# board.net
KiCad netlist of a schematic drawn in EAGLE
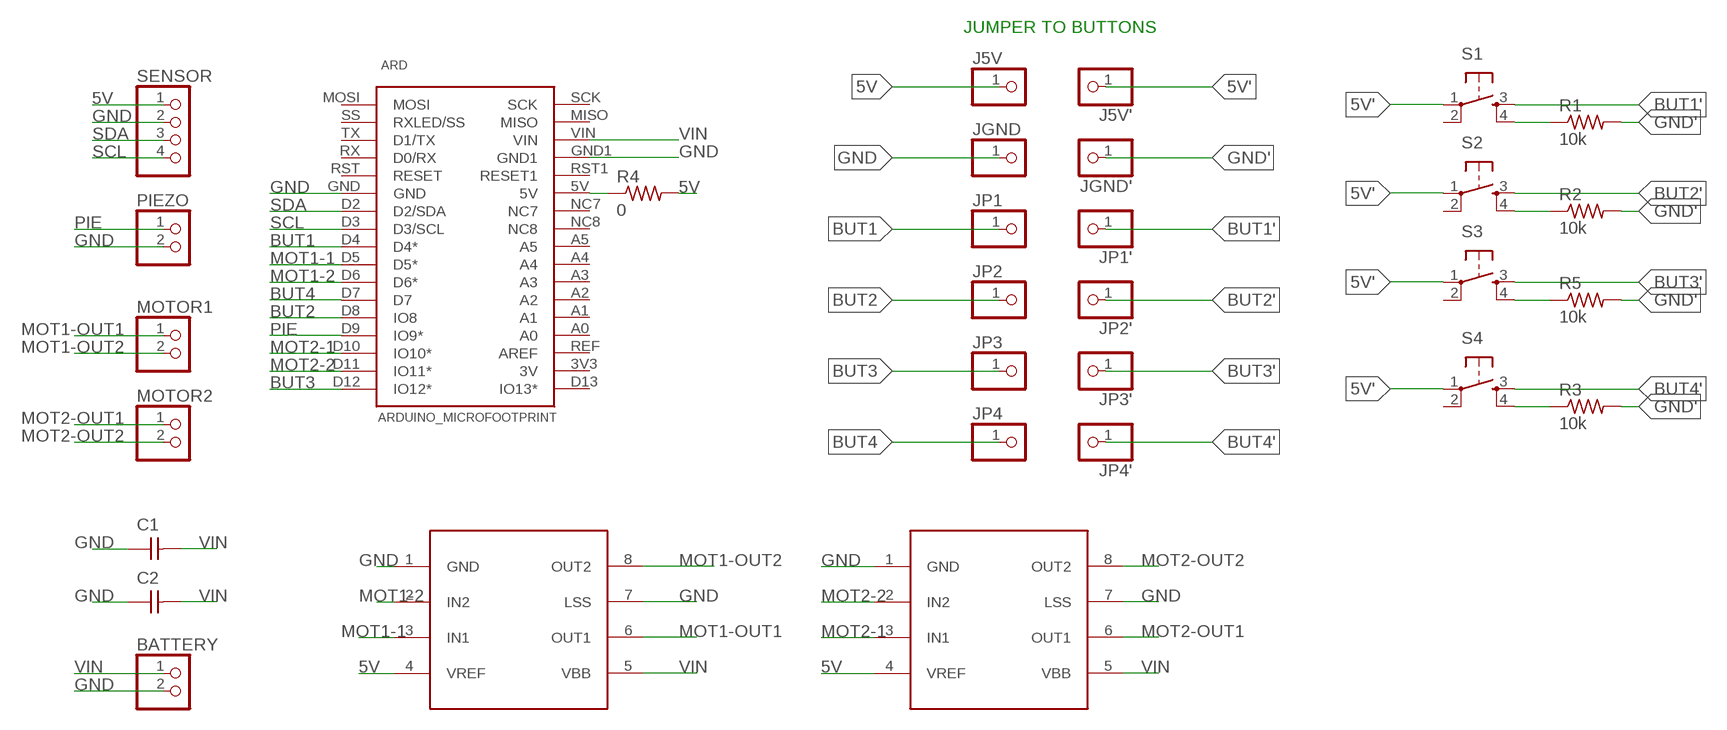
[diagram p0: schematic, sheet 1]

(export (version "E")
  (design (tool "Eeschema 10.0.6"))
  (components
    (comp (ref "ARD")
      (value "ARDUINO_MICROFOOTPRINT")
      (footprint "eagle-import:ARDUINO-MICRO")
      (libsource (lib "eagle-import") (part "ARDUINO_MICROFOOTPRINT"))
    )
    (comp (ref "BATTERY")
      (value "PINHD-1X2")
      (footprint "eagle-import:1X02")
      (libsource (lib "eagle-import") (part "PINHD-1X2"))
    )
    (comp (ref "C1")
      (value "CAP-UNPOLARIZEDFAB")
      (footprint "eagle-import:C1206FAB")
      (libsource (lib "eagle-import") (part "CAP-UNPOLARIZEDFAB"))
    )
    (comp (ref "C2")
      (value "CAP-UNPOLARIZEDFAB")
      (footprint "eagle-import:C1206FAB")
      (libsource (lib "eagle-import") (part "CAP-UNPOLARIZEDFAB"))
    )
    (comp (ref "J5V")
      (value "PINHD-1X1")
      (footprint "eagle-import:1X01")
      (libsource (lib "eagle-import") (part "PINHD-1X1"))
    )
    (comp (ref "J5V'")
      (value "PINHD-1X1")
      (footprint "eagle-import:1X01")
      (libsource (lib "eagle-import") (part "PINHD-1X1"))
    )
    (comp (ref "JGND")
      (value "PINHD-1X1")
      (footprint "eagle-import:1X01")
      (libsource (lib "eagle-import") (part "PINHD-1X1"))
    )
    (comp (ref "JGND'")
      (value "PINHD-1X1")
      (footprint "eagle-import:1X01")
      (libsource (lib "eagle-import") (part "PINHD-1X1"))
    )
    (comp (ref "JP1")
      (value "PINHD-1X1")
      (footprint "eagle-import:1X01")
      (libsource (lib "eagle-import") (part "PINHD-1X1"))
    )
    (comp (ref "JP1'")
      (value "PINHD-1X1")
      (footprint "eagle-import:1X01")
      (libsource (lib "eagle-import") (part "PINHD-1X1"))
    )
    (comp (ref "JP2")
      (value "PINHD-1X1")
      (footprint "eagle-import:1X01")
      (libsource (lib "eagle-import") (part "PINHD-1X1"))
    )
    (comp (ref "JP2'")
      (value "PINHD-1X1")
      (footprint "eagle-import:1X01")
      (libsource (lib "eagle-import") (part "PINHD-1X1"))
    )
    (comp (ref "JP3")
      (value "PINHD-1X1")
      (footprint "eagle-import:1X01")
      (libsource (lib "eagle-import") (part "PINHD-1X1"))
    )
    (comp (ref "JP3'")
      (value "PINHD-1X1")
      (footprint "eagle-import:1X01")
      (libsource (lib "eagle-import") (part "PINHD-1X1"))
    )
    (comp (ref "JP4")
      (value "PINHD-1X1")
      (footprint "eagle-import:1X01")
      (libsource (lib "eagle-import") (part "PINHD-1X1"))
    )
    (comp (ref "JP4'")
      (value "PINHD-1X1")
      (footprint "eagle-import:1X01")
      (libsource (lib "eagle-import") (part "PINHD-1X1"))
    )
    (comp (ref "MOT1")
      (value "A4953-H-BRIDGE-MOTOR-DRIVER")
      (footprint "eagle-import:SOIC8")
      (libsource (lib "eagle-import") (part "A4953-H-BRIDGE-MOTOR-DRIVER"))
    )
    (comp (ref "MOT2")
      (value "A4953-H-BRIDGE-MOTOR-DRIVER")
      (footprint "eagle-import:SOIC8")
      (libsource (lib "eagle-import") (part "A4953-H-BRIDGE-MOTOR-DRIVER"))
    )
    (comp (ref "MOTOR1")
      (value "PINHD-1X2")
      (footprint "eagle-import:1X02")
      (libsource (lib "eagle-import") (part "PINHD-1X2"))
    )
    (comp (ref "MOTOR2")
      (value "PINHD-1X2")
      (footprint "eagle-import:1X02")
      (libsource (lib "eagle-import") (part "PINHD-1X2"))
    )
    (comp (ref "PIEZO")
      (value "PINHD-1X2")
      (footprint "eagle-import:1X02")
      (libsource (lib "eagle-import") (part "PINHD-1X2"))
    )
    (comp (ref "R1")
      (value "10k")
      (footprint "eagle-import:R1206FAB")
      (libsource (lib "eagle-import") (part "RES-US1206FAB"))
    )
    (comp (ref "R2")
      (value "10k")
      (footprint "eagle-import:R1206FAB")
      (libsource (lib "eagle-import") (part "RES-US1206FAB"))
    )
    (comp (ref "R3")
      (value "10k")
      (footprint "eagle-import:R1206FAB")
      (libsource (lib "eagle-import") (part "RES-US1206FAB"))
    )
    (comp (ref "R4")
      (value "0")
      (footprint "eagle-import:R1206FAB")
      (libsource (lib "eagle-import") (part "RES-US1206FAB"))
    )
    (comp (ref "R5")
      (value "10k")
      (footprint "eagle-import:R1206FAB")
      (libsource (lib "eagle-import") (part "RES-US1206FAB"))
    )
    (comp (ref "S1")
      (value "6MM_SWITCH6MM_SWITCH")
      (footprint "eagle-import:6MM_SWITCH")
      (libsource (lib "eagle-import") (part "6MM_SWITCH6MM_SWITCH"))
    )
    (comp (ref "S2")
      (value "6MM_SWITCH6MM_SWITCH")
      (footprint "eagle-import:6MM_SWITCH")
      (libsource (lib "eagle-import") (part "6MM_SWITCH6MM_SWITCH"))
    )
    (comp (ref "S3")
      (value "6MM_SWITCH6MM_SWITCH")
      (footprint "eagle-import:6MM_SWITCH")
      (libsource (lib "eagle-import") (part "6MM_SWITCH6MM_SWITCH"))
    )
    (comp (ref "S4")
      (value "6MM_SWITCH6MM_SWITCH")
      (footprint "eagle-import:6MM_SWITCH")
      (libsource (lib "eagle-import") (part "6MM_SWITCH6MM_SWITCH"))
    )
    (comp (ref "SENSOR")
      (value "PINHD-1X4")
      (footprint "eagle-import:1X04")
      (libsource (lib "eagle-import") (part "PINHD-1X4"))
    )
  )
  (nets
    (net (code "1") (name "/MOT1-1") (class "Default")
      (node (ref "ARD") (pin "D5") (pinfunction "D5*_D5") (pintype "bidirectional"))
      (node (ref "MOT1") (pin "3") (pinfunction "IN1_3") (pintype "bidirectional"))
    )
    (net (code "2") (name "/MOT1-2") (class "Default")
      (node (ref "ARD") (pin "D6") (pinfunction "D6*_D6") (pintype "bidirectional"))
      (node (ref "MOT1") (pin "2") (pinfunction "IN2_2") (pintype "bidirectional"))
    )
    (net (code "3") (name "/MOT1-OUT1") (class "Default")
      (node (ref "MOT1") (pin "6") (pinfunction "OUT1_6") (pintype "bidirectional"))
      (node (ref "MOTOR1") (pin "1") (pinfunction "1_1") (pintype "passive"))
    )
    (net (code "4") (name "/MOT1-OUT2") (class "Default")
      (node (ref "MOT1") (pin "8") (pinfunction "OUT2_8") (pintype "bidirectional"))
      (node (ref "MOTOR1") (pin "2") (pinfunction "2_2") (pintype "passive"))
    )
    (net (code "5") (name "/MOT2-1") (class "Default")
      (node (ref "ARD") (pin "D10") (pinfunction "IO10*_D10") (pintype "bidirectional"))
      (node (ref "MOT2") (pin "3") (pinfunction "IN1_3") (pintype "bidirectional"))
    )
    (net (code "6") (name "/MOT2-2") (class "Default")
      (node (ref "ARD") (pin "D11") (pinfunction "IO11*_D11") (pintype "bidirectional"))
      (node (ref "MOT2") (pin "2") (pinfunction "IN2_2") (pintype "bidirectional"))
    )
    (net (code "7") (name "/MOT2-OUT1") (class "Default")
      (node (ref "MOT2") (pin "6") (pinfunction "OUT1_6") (pintype "bidirectional"))
      (node (ref "MOTOR2") (pin "1") (pinfunction "1_1") (pintype "passive"))
    )
    (net (code "8") (name "/MOT2-OUT2") (class "Default")
      (node (ref "MOT2") (pin "8") (pinfunction "OUT2_8") (pintype "bidirectional"))
      (node (ref "MOTOR2") (pin "2") (pinfunction "2_2") (pintype "passive"))
    )
    (net (code "9") (name "/PIE") (class "Default")
      (node (ref "ARD") (pin "D9") (pinfunction "IO9*_D9") (pintype "bidirectional"))
      (node (ref "PIEZO") (pin "1") (pinfunction "1_1") (pintype "passive"))
    )
    (net (code "10") (name "/SCL") (class "Default")
      (node (ref "ARD") (pin "D3") (pinfunction "D3/SCL_D3") (pintype "bidirectional"))
      (node (ref "SENSOR") (pin "4") (pinfunction "4_4") (pintype "passive"))
    )
    (net (code "11") (name "/SDA") (class "Default")
      (node (ref "ARD") (pin "D2") (pinfunction "D2/SDA_D2") (pintype "bidirectional"))
      (node (ref "SENSOR") (pin "3") (pinfunction "3_3") (pintype "passive"))
    )
    (net (code "12") (name "/VIN") (class "Default")
      (node (ref "ARD") (pin "VIN") (pinfunction "VIN_VIN") (pintype "bidirectional"))
      (node (ref "BATTERY") (pin "1") (pinfunction "1_1") (pintype "passive"))
      (node (ref "C1") (pin "2") (pinfunction "2_2") (pintype "passive"))
      (node (ref "C2") (pin "2") (pinfunction "2_2") (pintype "passive"))
      (node (ref "MOT1") (pin "5") (pinfunction "VBB_5") (pintype "bidirectional"))
      (node (ref "MOT2") (pin "5") (pinfunction "VBB_5") (pintype "bidirectional"))
    )
    (net (code "13") (name "5V") (class "Default")
      (node (ref "J5V") (pin "1") (pinfunction "1_1") (pintype "passive"))
      (node (ref "MOT1") (pin "4") (pinfunction "VREF_4") (pintype "bidirectional"))
      (node (ref "MOT2") (pin "4") (pinfunction "VREF_4") (pintype "bidirectional"))
      (node (ref "R4") (pin "2") (pinfunction "2_2") (pintype "passive"))
      (node (ref "SENSOR") (pin "1") (pinfunction "1_1") (pintype "passive"))
    )
    (net (code "14") (name "5V'") (class "Default")
      (node (ref "J5V'") (pin "1") (pinfunction "1_1") (pintype "passive"))
      (node (ref "S1") (pin "1") (pinfunction "P_1") (pintype "passive"))
      (node (ref "S2") (pin "1") (pinfunction "P_1") (pintype "passive"))
      (node (ref "S3") (pin "1") (pinfunction "P_1") (pintype "passive"))
      (node (ref "S4") (pin "1") (pinfunction "P_1") (pintype "passive"))
    )
    (net (code "15") (name "BUT1") (class "Default")
      (node (ref "ARD") (pin "D4") (pinfunction "D4*_D4") (pintype "bidirectional"))
      (node (ref "JP1") (pin "1") (pinfunction "1_1") (pintype "passive"))
    )
    (net (code "16") (name "BUT1'") (class "Default")
      (node (ref "JP1'") (pin "1") (pinfunction "1_1") (pintype "passive"))
      (node (ref "S1") (pin "3") (pinfunction "S_3") (pintype "passive"))
    )
    (net (code "17") (name "BUT2") (class "Default")
      (node (ref "ARD") (pin "D8") (pinfunction "IO8_D8") (pintype "bidirectional"))
      (node (ref "JP2") (pin "1") (pinfunction "1_1") (pintype "passive"))
    )
    (net (code "18") (name "BUT2'") (class "Default")
      (node (ref "JP2'") (pin "1") (pinfunction "1_1") (pintype "passive"))
      (node (ref "S2") (pin "3") (pinfunction "S_3") (pintype "passive"))
    )
    (net (code "19") (name "BUT3") (class "Default")
      (node (ref "ARD") (pin "D12") (pinfunction "IO12*_D12") (pintype "bidirectional"))
      (node (ref "JP3") (pin "1") (pinfunction "1_1") (pintype "passive"))
    )
    (net (code "20") (name "BUT3'") (class "Default")
      (node (ref "JP3'") (pin "1") (pinfunction "1_1") (pintype "passive"))
      (node (ref "S3") (pin "3") (pinfunction "S_3") (pintype "passive"))
    )
    (net (code "21") (name "BUT4") (class "Default")
      (node (ref "ARD") (pin "D7") (pinfunction "D7_D7") (pintype "bidirectional"))
      (node (ref "JP4") (pin "1") (pinfunction "1_1") (pintype "passive"))
    )
    (net (code "22") (name "BUT4'") (class "Default")
      (node (ref "JP4'") (pin "1") (pinfunction "1_1") (pintype "passive"))
      (node (ref "S4") (pin "3") (pinfunction "S_3") (pintype "passive"))
    )
    (net (code "23") (name "GND") (class "Default")
      (node (ref "ARD") (pin "GND") (pinfunction "GND_GND") (pintype "bidirectional"))
      (node (ref "ARD") (pin "GND1") (pinfunction "GND1_GND1") (pintype "bidirectional"))
      (node (ref "BATTERY") (pin "2") (pinfunction "2_2") (pintype "passive"))
      (node (ref "C1") (pin "1") (pinfunction "1_1") (pintype "passive"))
      (node (ref "C2") (pin "1") (pinfunction "1_1") (pintype "passive"))
      (node (ref "JGND") (pin "1") (pinfunction "1_1") (pintype "passive"))
      (node (ref "MOT1") (pin "1") (pinfunction "GND_1") (pintype "bidirectional"))
      (node (ref "MOT1") (pin "7") (pinfunction "LSS_7") (pintype "bidirectional"))
      (node (ref "MOT2") (pin "1") (pinfunction "GND_1") (pintype "bidirectional"))
      (node (ref "MOT2") (pin "7") (pinfunction "LSS_7") (pintype "bidirectional"))
      (node (ref "PIEZO") (pin "2") (pinfunction "2_2") (pintype "passive"))
      (node (ref "SENSOR") (pin "2") (pinfunction "2_2") (pintype "passive"))
    )
    (net (code "24") (name "GND'") (class "Default")
      (node (ref "JGND'") (pin "1") (pinfunction "1_1") (pintype "passive"))
      (node (ref "R1") (pin "2") (pinfunction "2_2") (pintype "passive"))
      (node (ref "R2") (pin "2") (pinfunction "2_2") (pintype "passive"))
      (node (ref "R3") (pin "2") (pinfunction "2_2") (pintype "passive"))
      (node (ref "R5") (pin "2") (pinfunction "2_2") (pintype "passive"))
    )
    (net (code "25") (name "Net-(ARD-Pad5V)") (class "Default")
      (node (ref "ARD") (pin "5V") (pinfunction "5V_5V") (pintype "bidirectional"))
      (node (ref "R4") (pin "1") (pinfunction "1_1") (pintype "passive"))
    )
    (net (code "26") (name "Net-(S1-S1)") (class "Default")
      (node (ref "R1") (pin "1") (pinfunction "1_1") (pintype "passive"))
      (node (ref "S1") (pin "4") (pinfunction "S1_4") (pintype "passive"))
    )
    (net (code "27") (name "Net-(S2-S1)") (class "Default")
      (node (ref "R2") (pin "1") (pinfunction "1_1") (pintype "passive"))
      (node (ref "S2") (pin "4") (pinfunction "S1_4") (pintype "passive"))
    )
    (net (code "28") (name "Net-(S3-S1)") (class "Default")
      (node (ref "R5") (pin "1") (pinfunction "1_1") (pintype "passive"))
      (node (ref "S3") (pin "4") (pinfunction "S1_4") (pintype "passive"))
    )
    (net (code "29") (name "Net-(S4-S1)") (class "Default")
      (node (ref "R3") (pin "1") (pinfunction "1_1") (pintype "passive"))
      (node (ref "S4") (pin "4") (pinfunction "S1_4") (pintype "passive"))
    )
    (net (code "30") (name "unconnected-(ARD-3V-Pad3V3)") (class "Default")
      (node (ref "ARD") (pin "3V3") (pinfunction "3V_3V3") (pintype "bidirectional"))
    )
    (net (code "31") (name "unconnected-(ARD-AREF-PadREF)") (class "Default")
      (node (ref "ARD") (pin "REF") (pinfunction "AREF_REF") (pintype "bidirectional"))
    )
    (net (code "32") (name "unconnected-(ARD-D0{slash}RX-PadRX)") (class "Default")
      (node (ref "ARD") (pin "RX") (pinfunction "D0/RX_RX") (pintype "bidirectional"))
    )
    (net (code "33") (name "unconnected-(ARD-D1{slash}TX-PadTX)") (class "Default")
      (node (ref "ARD") (pin "TX") (pinfunction "D1/TX_TX") (pintype "bidirectional"))
    )
    (net (code "34") (name "unconnected-(ARD-IO13*-PadD13)") (class "Default")
      (node (ref "ARD") (pin "D13") (pinfunction "IO13*_D13") (pintype "bidirectional"))
    )
    (net (code "35") (name "unconnected-(ARD-PadA0)") (class "Default")
      (node (ref "ARD") (pin "A0") (pinfunction "A0_A0") (pintype "bidirectional"))
    )
    (net (code "36") (name "unconnected-(ARD-PadA1)") (class "Default")
      (node (ref "ARD") (pin "A1") (pinfunction "A1_A1") (pintype "bidirectional"))
    )
    (net (code "37") (name "unconnected-(ARD-PadA2)") (class "Default")
      (node (ref "ARD") (pin "A2") (pinfunction "A2_A2") (pintype "bidirectional"))
    )
    (net (code "38") (name "unconnected-(ARD-PadA3)") (class "Default")
      (node (ref "ARD") (pin "A3") (pinfunction "A3_A3") (pintype "bidirectional"))
    )
    (net (code "39") (name "unconnected-(ARD-PadA4)") (class "Default")
      (node (ref "ARD") (pin "A4") (pinfunction "A4_A4") (pintype "bidirectional"))
    )
    (net (code "40") (name "unconnected-(ARD-PadA5)") (class "Default")
      (node (ref "ARD") (pin "A5") (pinfunction "A5_A5") (pintype "bidirectional"))
    )
    (net (code "41") (name "unconnected-(ARD-PadMISO)") (class "Default")
      (node (ref "ARD") (pin "MISO") (pinfunction "MISO_MISO") (pintype "bidirectional"))
    )
    (net (code "42") (name "unconnected-(ARD-PadMOSI)") (class "Default")
      (node (ref "ARD") (pin "MOSI") (pinfunction "MOSI_MOSI") (pintype "bidirectional"))
    )
    (net (code "43") (name "unconnected-(ARD-PadNC7)") (class "Default")
      (node (ref "ARD") (pin "NC7") (pinfunction "NC7_NC7") (pintype "bidirectional"))
    )
    (net (code "44") (name "unconnected-(ARD-PadNC8)") (class "Default")
      (node (ref "ARD") (pin "NC8") (pinfunction "NC8_NC8") (pintype "bidirectional"))
    )
    (net (code "45") (name "unconnected-(ARD-PadSCK)") (class "Default")
      (node (ref "ARD") (pin "SCK") (pinfunction "SCK_SCK") (pintype "bidirectional"))
    )
    (net (code "46") (name "unconnected-(ARD-RESET-PadRST)") (class "Default")
      (node (ref "ARD") (pin "RST") (pinfunction "RESET_RST") (pintype "bidirectional"))
    )
    (net (code "47") (name "unconnected-(ARD-RESET1-PadRST1)") (class "Default")
      (node (ref "ARD") (pin "RST1") (pinfunction "RESET1_RST1") (pintype "bidirectional"))
    )
    (net (code "48") (name "unconnected-(ARD-RXLED{slash}SS-PadSS)") (class "Default")
      (node (ref "ARD") (pin "SS") (pinfunction "RXLED/SS_SS") (pintype "bidirectional"))
    )
    (net (code "49") (name "unconnected-(S1-P1-Pad2)") (class "Default")
      (node (ref "S1") (pin "2") (pinfunction "P1_2") (pintype "passive"))
    )
    (net (code "50") (name "unconnected-(S2-P1-Pad2)") (class "Default")
      (node (ref "S2") (pin "2") (pinfunction "P1_2") (pintype "passive"))
    )
    (net (code "51") (name "unconnected-(S3-P1-Pad2)") (class "Default")
      (node (ref "S3") (pin "2") (pinfunction "P1_2") (pintype "passive"))
    )
    (net (code "52") (name "unconnected-(S4-P1-Pad2)") (class "Default")
      (node (ref "S4") (pin "2") (pinfunction "P1_2") (pintype "passive"))
    )
  )
)
